# ab_v11.net
KiCad netlist of a schematic drawn in EAGLE
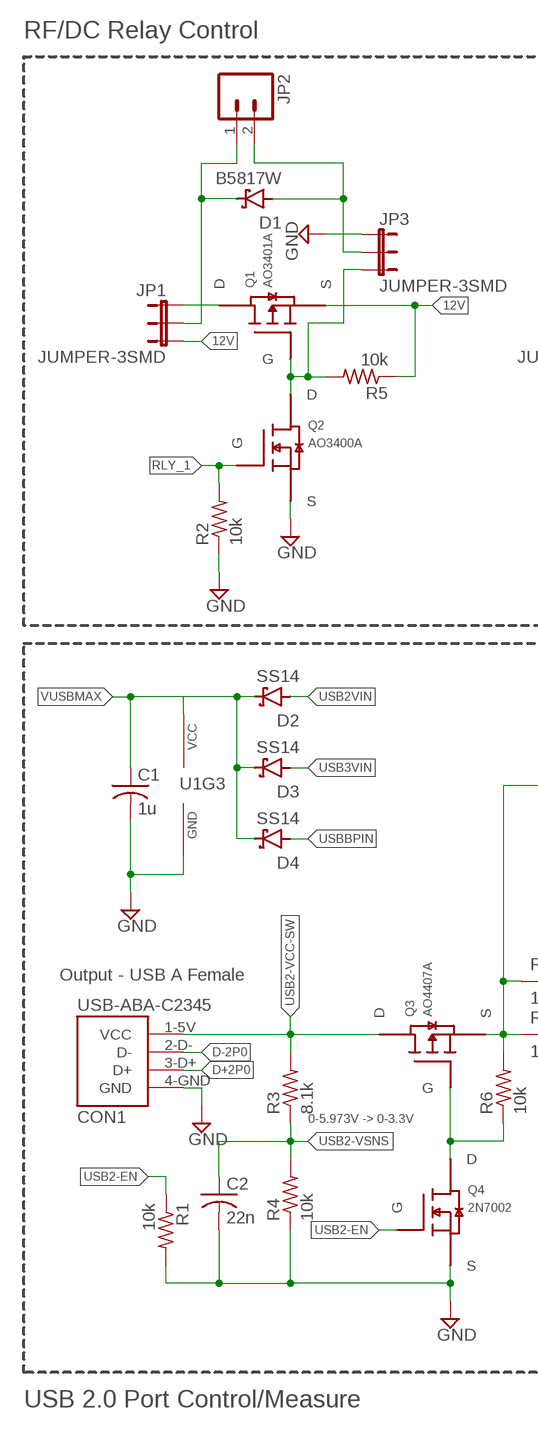
[diagram p0: schematic, sheet 1, part 1 of 2]
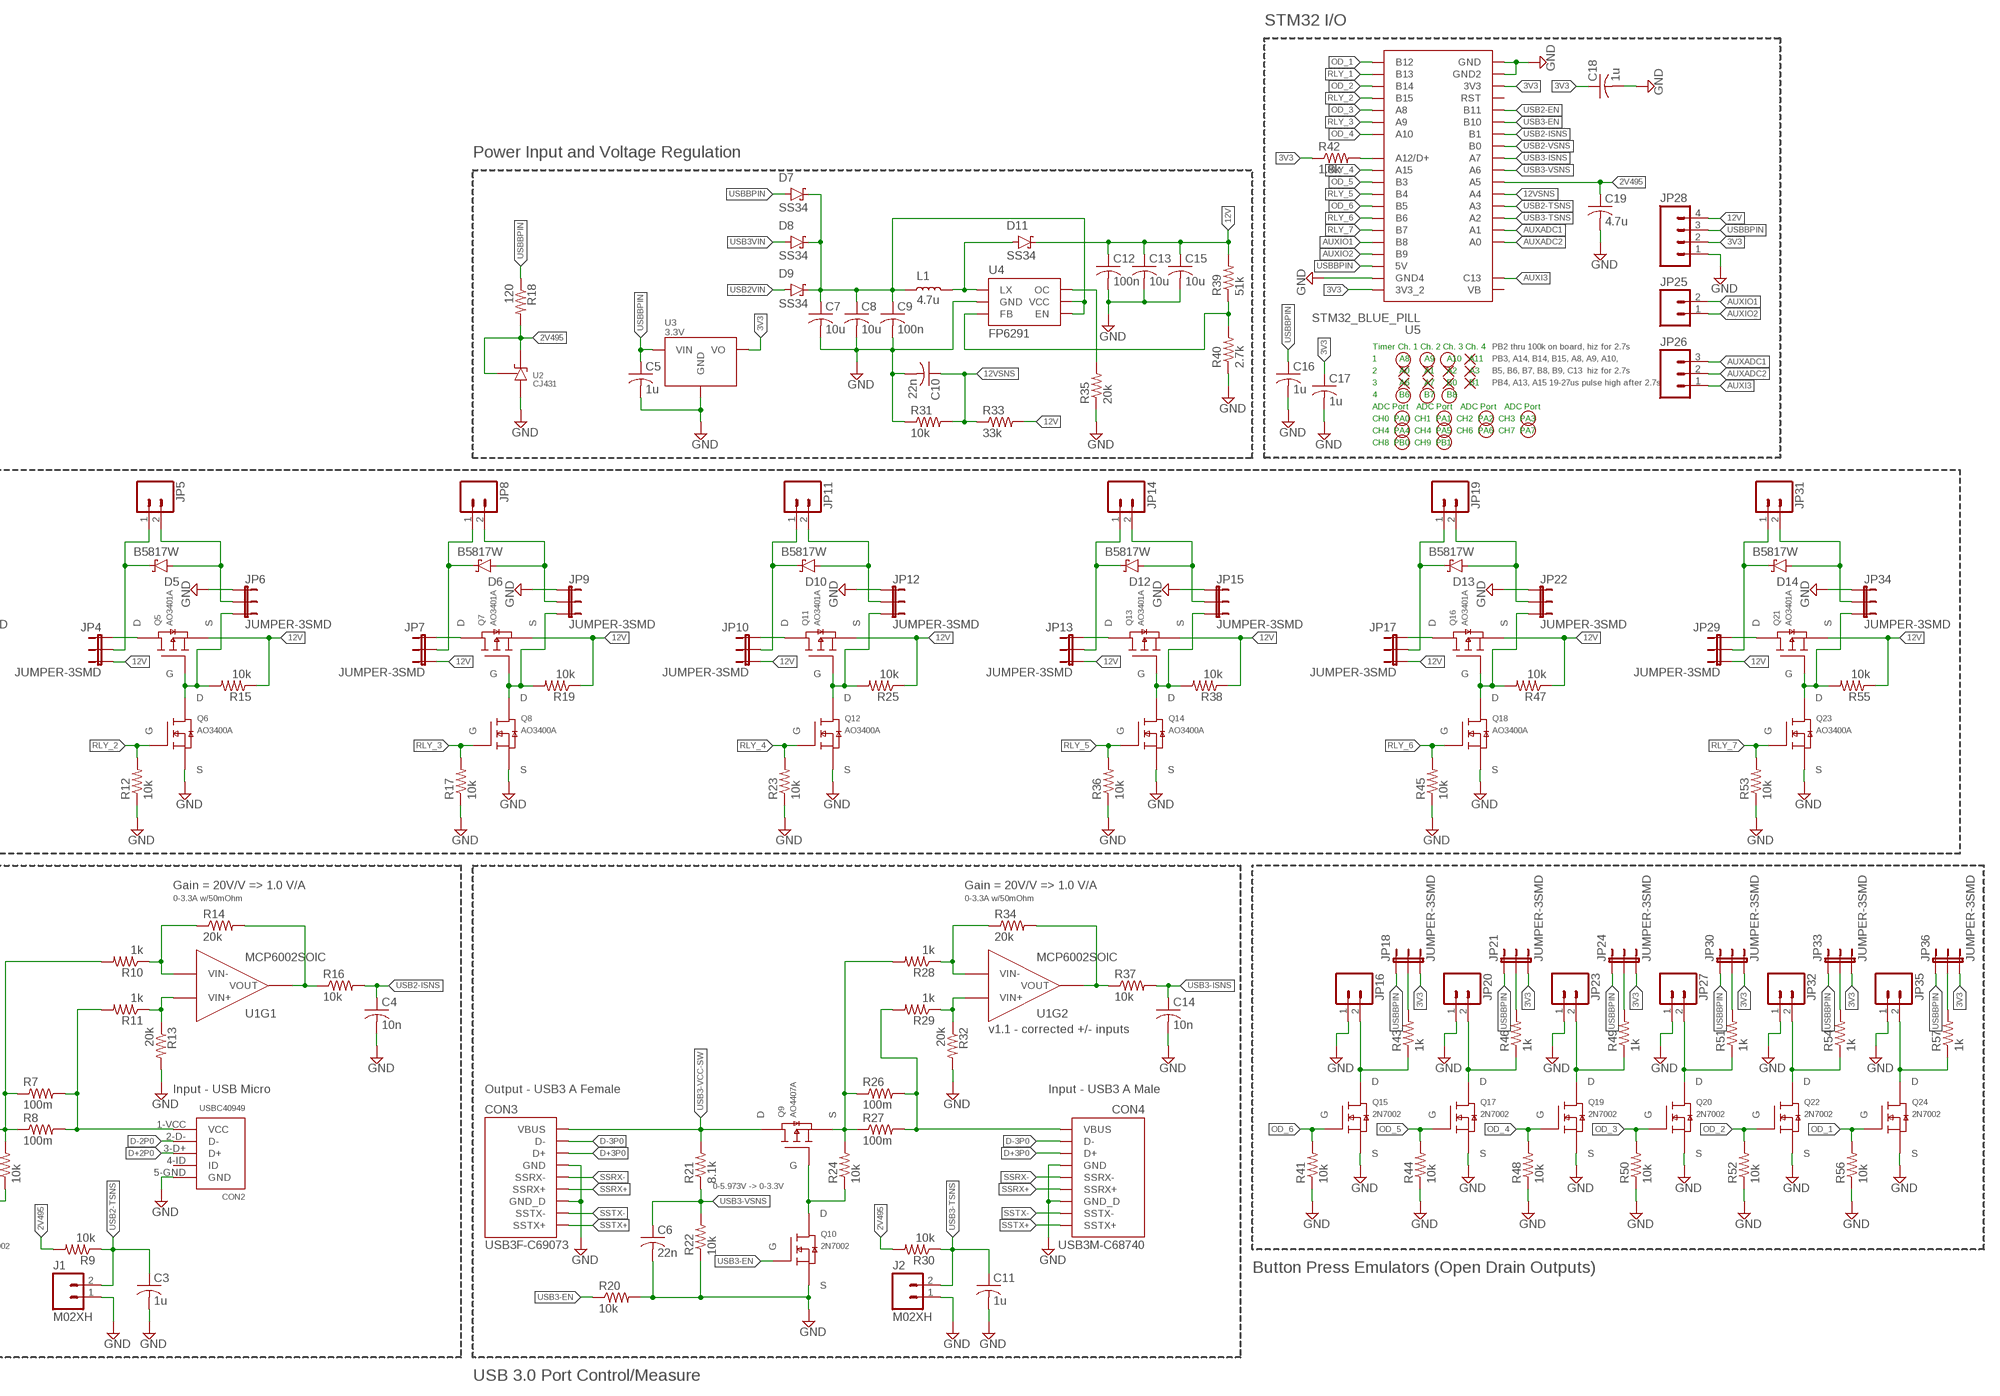
[diagram p1: schematic, sheet 1, part 2 of 2]

(export (version "E")
  (design (tool "Eeschema 10.0.6"))
  (components
    (comp (ref "C1")
      (value "1u")
      (footprint "eagle-import:C0402")
      (libsource (lib "eagle-import") (part "C-USC0402"))
    )
    (comp (ref "C2")
      (value "22n")
      (footprint "eagle-import:C0402")
      (libsource (lib "eagle-import") (part "C-USC0402"))
    )
    (comp (ref "C3")
      (value "1u")
      (footprint "eagle-import:C0402")
      (libsource (lib "eagle-import") (part "C-USC0402"))
    )
    (comp (ref "C4")
      (value "10n")
      (footprint "eagle-import:C0402")
      (libsource (lib "eagle-import") (part "C-USC0402"))
    )
    (comp (ref "C5")
      (value "1u")
      (footprint "eagle-import:C0402")
      (libsource (lib "eagle-import") (part "C-USC0402"))
    )
    (comp (ref "C6")
      (value "22n")
      (footprint "eagle-import:C0402")
      (libsource (lib "eagle-import") (part "C-USC0402"))
    )
    (comp (ref "C7")
      (value "10u")
      (footprint "eagle-import:C0603")
      (libsource (lib "eagle-import") (part "C-USC0603"))
    )
    (comp (ref "C8")
      (value "10u")
      (footprint "eagle-import:C0603")
      (libsource (lib "eagle-import") (part "C-USC0603"))
    )
    (comp (ref "C9")
      (value "100n")
      (footprint "eagle-import:C0402")
      (libsource (lib "eagle-import") (part "C-USC0402"))
    )
    (comp (ref "C10")
      (value "22n")
      (footprint "eagle-import:C0402")
      (libsource (lib "eagle-import") (part "C-USC0402"))
    )
    (comp (ref "C11")
      (value "1u")
      (footprint "eagle-import:C0402")
      (libsource (lib "eagle-import") (part "C-USC0402"))
    )
    (comp (ref "C12")
      (value "100n")
      (footprint "eagle-import:C0402")
      (libsource (lib "eagle-import") (part "C-USC0402"))
    )
    (comp (ref "C13")
      (value "10u")
      (footprint "eagle-import:C0805")
      (libsource (lib "eagle-import") (part "C-USC0805"))
    )
    (comp (ref "C14")
      (value "10n")
      (footprint "eagle-import:C0402")
      (libsource (lib "eagle-import") (part "C-USC0402"))
    )
    (comp (ref "C15")
      (value "10u")
      (footprint "eagle-import:C0805")
      (libsource (lib "eagle-import") (part "C-USC0805"))
    )
    (comp (ref "C16")
      (value "1u")
      (footprint "eagle-import:C0402")
      (libsource (lib "eagle-import") (part "C-USC0402"))
    )
    (comp (ref "C17")
      (value "1u")
      (footprint "eagle-import:C0402")
      (libsource (lib "eagle-import") (part "C-USC0402"))
    )
    (comp (ref "C18")
      (value "1u")
      (footprint "eagle-import:C0402")
      (libsource (lib "eagle-import") (part "C-USC0402"))
    )
    (comp (ref "C19")
      (value "4.7u")
      (footprint "eagle-import:C0402")
      (libsource (lib "eagle-import") (part "C-USC0402"))
    )
    (comp (ref "CON1")
      (value "USB-ABA-C2345")
      (footprint "eagle-import:USB_A_C2345")
      (libsource (lib "eagle-import") (part "USB-ABA-C2345"))
    )
    (comp (ref "CON2")
      (value "USBC40949")
      (footprint "eagle-import:MICRO_USB-B_C40949")
      (libsource (lib "eagle-import") (part "USBC40949"))
    )
    (comp (ref "CON3")
      (value "USB3F-C69073")
      (footprint "eagle-import:USB3-F-C69073")
      (libsource (lib "eagle-import") (part "USB3F-C69073"))
    )
    (comp (ref "CON4")
      (value "USB3M-C68740")
      (footprint "eagle-import:USB3-M-C68740")
      (libsource (lib "eagle-import") (part "USB3M-C68740"))
    )
    (comp (ref "D1")
      (value "B5817W")
      (footprint "eagle-import:SOD123W")
      (libsource (lib "eagle-import") (part "PMEG3020ER"))
    )
    (comp (ref "D2")
      (value "SS14")
      (footprint "eagle-import:SMA")
      (libsource (lib "eagle-import") (part "DIODE_SCHOTTKY_SMSSMA"))
    )
    (comp (ref "D3")
      (value "SS14")
      (footprint "eagle-import:SMA")
      (libsource (lib "eagle-import") (part "DIODE_SCHOTTKY_SMSSMA"))
    )
    (comp (ref "D4")
      (value "SS14")
      (footprint "eagle-import:SMA")
      (libsource (lib "eagle-import") (part "DIODE_SCHOTTKY_SMSSMA"))
    )
    (comp (ref "D5")
      (value "B5817W")
      (footprint "eagle-import:SOD123W")
      (libsource (lib "eagle-import") (part "PMEG3020ER"))
    )
    (comp (ref "D6")
      (value "B5817W")
      (footprint "eagle-import:SOD123W")
      (libsource (lib "eagle-import") (part "PMEG3020ER"))
    )
    (comp (ref "D7")
      (value "SS34")
      (footprint "eagle-import:SMA")
      (libsource (lib "eagle-import") (part "DIODE_SCHOTTKY_SMSSMA"))
    )
    (comp (ref "D8")
      (value "SS34")
      (footprint "eagle-import:SMA")
      (libsource (lib "eagle-import") (part "DIODE_SCHOTTKY_SMSSMA"))
    )
    (comp (ref "D9")
      (value "SS34")
      (footprint "eagle-import:SMA")
      (libsource (lib "eagle-import") (part "DIODE_SCHOTTKY_SMSSMA"))
    )
    (comp (ref "D10")
      (value "B5817W")
      (footprint "eagle-import:SOD123W")
      (libsource (lib "eagle-import") (part "PMEG3020ER"))
    )
    (comp (ref "D11")
      (value "SS34")
      (footprint "eagle-import:SMA")
      (libsource (lib "eagle-import") (part "DIODE_SCHOTTKY_SMSSMA"))
    )
    (comp (ref "D12")
      (value "B5817W")
      (footprint "eagle-import:SOD123W")
      (libsource (lib "eagle-import") (part "PMEG3020ER"))
    )
    (comp (ref "D13")
      (value "B5817W")
      (footprint "eagle-import:SOD123W")
      (libsource (lib "eagle-import") (part "PMEG3020ER"))
    )
    (comp (ref "D14")
      (value "B5817W")
      (footprint "eagle-import:SOD123W")
      (libsource (lib "eagle-import") (part "PMEG3020ER"))
    )
    (comp (ref "J1")
      (value "M02XH")
      (footprint "eagle-import:B2B-XH-A")
      (libsource (lib "eagle-import") (part "M02XH"))
    )
    (comp (ref "J2")
      (value "M02XH")
      (footprint "eagle-import:B2B-XH-A")
      (libsource (lib "eagle-import") (part "M02XH"))
    )
    (comp (ref "JP1")
      (value "JUMPER-3SMD")
      (footprint "eagle-import:SJ_3")
      (libsource (lib "eagle-import") (part "JUMPER-3SMD"))
    )
    (comp (ref "JP2")
      (value "M02PTH")
      (footprint "eagle-import:1X02")
      (libsource (lib "eagle-import") (part "M02PTH"))
    )
    (comp (ref "JP3")
      (value "JUMPER-3SMD")
      (footprint "eagle-import:SJ_3")
      (libsource (lib "eagle-import") (part "JUMPER-3SMD"))
    )
    (comp (ref "JP4")
      (value "JUMPER-3SMD")
      (footprint "eagle-import:SJ_3")
      (libsource (lib "eagle-import") (part "JUMPER-3SMD"))
    )
    (comp (ref "JP5")
      (value "M02PTH")
      (footprint "eagle-import:1X02")
      (libsource (lib "eagle-import") (part "M02PTH"))
    )
    (comp (ref "JP6")
      (value "JUMPER-3SMD")
      (footprint "eagle-import:SJ_3")
      (libsource (lib "eagle-import") (part "JUMPER-3SMD"))
    )
    (comp (ref "JP7")
      (value "JUMPER-3SMD")
      (footprint "eagle-import:SJ_3")
      (libsource (lib "eagle-import") (part "JUMPER-3SMD"))
    )
    (comp (ref "JP8")
      (value "M02PTH")
      (footprint "eagle-import:1X02")
      (libsource (lib "eagle-import") (part "M02PTH"))
    )
    (comp (ref "JP9")
      (value "JUMPER-3SMD")
      (footprint "eagle-import:SJ_3")
      (libsource (lib "eagle-import") (part "JUMPER-3SMD"))
    )
    (comp (ref "JP10")
      (value "JUMPER-3SMD")
      (footprint "eagle-import:SJ_3")
      (libsource (lib "eagle-import") (part "JUMPER-3SMD"))
    )
    (comp (ref "JP11")
      (value "M02PTH")
      (footprint "eagle-import:1X02")
      (libsource (lib "eagle-import") (part "M02PTH"))
    )
    (comp (ref "JP12")
      (value "JUMPER-3SMD")
      (footprint "eagle-import:SJ_3")
      (libsource (lib "eagle-import") (part "JUMPER-3SMD"))
    )
    (comp (ref "JP13")
      (value "JUMPER-3SMD")
      (footprint "eagle-import:SJ_3")
      (libsource (lib "eagle-import") (part "JUMPER-3SMD"))
    )
    (comp (ref "JP14")
      (value "M02PTH")
      (footprint "eagle-import:1X02")
      (libsource (lib "eagle-import") (part "M02PTH"))
    )
    (comp (ref "JP15")
      (value "JUMPER-3SMD")
      (footprint "eagle-import:SJ_3")
      (libsource (lib "eagle-import") (part "JUMPER-3SMD"))
    )
    (comp (ref "JP16")
      (value "M02PTH")
      (footprint "eagle-import:1X02")
      (libsource (lib "eagle-import") (part "M02PTH"))
    )
    (comp (ref "JP17")
      (value "JUMPER-3SMD")
      (footprint "eagle-import:SJ_3")
      (libsource (lib "eagle-import") (part "JUMPER-3SMD"))
    )
    (comp (ref "JP18")
      (value "JUMPER-3SMD")
      (footprint "eagle-import:SJ_3")
      (libsource (lib "eagle-import") (part "JUMPER-3SMD"))
    )
    (comp (ref "JP19")
      (value "M02PTH")
      (footprint "eagle-import:1X02")
      (libsource (lib "eagle-import") (part "M02PTH"))
    )
    (comp (ref "JP20")
      (value "M02PTH")
      (footprint "eagle-import:1X02")
      (libsource (lib "eagle-import") (part "M02PTH"))
    )
    (comp (ref "JP21")
      (value "JUMPER-3SMD")
      (footprint "eagle-import:SJ_3")
      (libsource (lib "eagle-import") (part "JUMPER-3SMD"))
    )
    (comp (ref "JP22")
      (value "JUMPER-3SMD")
      (footprint "eagle-import:SJ_3")
      (libsource (lib "eagle-import") (part "JUMPER-3SMD"))
    )
    (comp (ref "JP23")
      (value "M02PTH")
      (footprint "eagle-import:1X02")
      (libsource (lib "eagle-import") (part "M02PTH"))
    )
    (comp (ref "JP24")
      (value "JUMPER-3SMD")
      (footprint "eagle-import:SJ_3")
      (libsource (lib "eagle-import") (part "JUMPER-3SMD"))
    )
    (comp (ref "JP25")
      (value "M02PTH")
      (footprint "eagle-import:1X02")
      (libsource (lib "eagle-import") (part "M02PTH"))
    )
    (comp (ref "JP26")
      (value "M03PTH")
      (footprint "eagle-import:1X03")
      (libsource (lib "eagle-import") (part "M03PTH"))
    )
    (comp (ref "JP27")
      (value "M02PTH")
      (footprint "eagle-import:1X02")
      (libsource (lib "eagle-import") (part "M02PTH"))
    )
    (comp (ref "JP28")
      (value "M04PTH")
      (footprint "eagle-import:1X04")
      (libsource (lib "eagle-import") (part "M04PTH"))
    )
    (comp (ref "JP29")
      (value "JUMPER-3SMD")
      (footprint "eagle-import:SJ_3")
      (libsource (lib "eagle-import") (part "JUMPER-3SMD"))
    )
    (comp (ref "JP30")
      (value "JUMPER-3SMD")
      (footprint "eagle-import:SJ_3")
      (libsource (lib "eagle-import") (part "JUMPER-3SMD"))
    )
    (comp (ref "JP31")
      (value "M02PTH")
      (footprint "eagle-import:1X02")
      (libsource (lib "eagle-import") (part "M02PTH"))
    )
    (comp (ref "JP32")
      (value "M02PTH")
      (footprint "eagle-import:1X02")
      (libsource (lib "eagle-import") (part "M02PTH"))
    )
    (comp (ref "JP33")
      (value "JUMPER-3SMD")
      (footprint "eagle-import:SJ_3")
      (libsource (lib "eagle-import") (part "JUMPER-3SMD"))
    )
    (comp (ref "JP34")
      (value "JUMPER-3SMD")
      (footprint "eagle-import:SJ_3")
      (libsource (lib "eagle-import") (part "JUMPER-3SMD"))
    )
    (comp (ref "JP35")
      (value "M02PTH")
      (footprint "eagle-import:1X02")
      (libsource (lib "eagle-import") (part "M02PTH"))
    )
    (comp (ref "JP36")
      (value "JUMPER-3SMD")
      (footprint "eagle-import:SJ_3")
      (libsource (lib "eagle-import") (part "JUMPER-3SMD"))
    )
    (comp (ref "L1")
      (value "4.7u")
      (footprint "eagle-import:INDUCTOR_6X6")
      (libsource (lib "eagle-import") (part "INDUCTOR6X6"))
    )
    (comp (ref "Q1")
      (value "AO3401A")
      (footprint "eagle-import:SOT23")
      (libsource (lib "eagle-import") (part "AO3401A"))
    )
    (comp (ref "Q2")
      (value "AO3400A")
      (footprint "eagle-import:SOT23")
      (libsource (lib "eagle-import") (part "2N7002P"))
    )
    (comp (ref "Q3")
      (value "AO4407A")
      (footprint "eagle-import:8-SOIC")
      (libsource (lib "eagle-import") (part "P-MOSFET-SOIC8"))
    )
    (comp (ref "Q4")
      (value "2N7002")
      (footprint "eagle-import:SOT23")
      (libsource (lib "eagle-import") (part "2N7002P"))
    )
    (comp (ref "Q5")
      (value "AO3401A")
      (footprint "eagle-import:SOT23")
      (libsource (lib "eagle-import") (part "AO3401A"))
    )
    (comp (ref "Q6")
      (value "AO3400A")
      (footprint "eagle-import:SOT23")
      (libsource (lib "eagle-import") (part "2N7002P"))
    )
    (comp (ref "Q7")
      (value "AO3401A")
      (footprint "eagle-import:SOT23")
      (libsource (lib "eagle-import") (part "AO3401A"))
    )
    (comp (ref "Q8")
      (value "AO3400A")
      (footprint "eagle-import:SOT23")
      (libsource (lib "eagle-import") (part "2N7002P"))
    )
    (comp (ref "Q9")
      (value "AO4407A")
      (footprint "eagle-import:8-SOIC")
      (libsource (lib "eagle-import") (part "P-MOSFET-SOIC8"))
    )
    (comp (ref "Q10")
      (value "2N7002")
      (footprint "eagle-import:SOT23")
      (libsource (lib "eagle-import") (part "2N7002P"))
    )
    (comp (ref "Q11")
      (value "AO3401A")
      (footprint "eagle-import:SOT23")
      (libsource (lib "eagle-import") (part "AO3401A"))
    )
    (comp (ref "Q12")
      (value "AO3400A")
      (footprint "eagle-import:SOT23")
      (libsource (lib "eagle-import") (part "2N7002P"))
    )
    (comp (ref "Q13")
      (value "AO3401A")
      (footprint "eagle-import:SOT23")
      (libsource (lib "eagle-import") (part "AO3401A"))
    )
    (comp (ref "Q14")
      (value "AO3400A")
      (footprint "eagle-import:SOT23")
      (libsource (lib "eagle-import") (part "2N7002P"))
    )
    (comp (ref "Q15")
      (value "2N7002")
      (footprint "eagle-import:SOT23")
      (libsource (lib "eagle-import") (part "2N7002P"))
    )
    (comp (ref "Q16")
      (value "AO3401A")
      (footprint "eagle-import:SOT23")
      (libsource (lib "eagle-import") (part "AO3401A"))
    )
    (comp (ref "Q17")
      (value "2N7002")
      (footprint "eagle-import:SOT23")
      (libsource (lib "eagle-import") (part "2N7002P"))
    )
    (comp (ref "Q18")
      (value "AO3400A")
      (footprint "eagle-import:SOT23")
      (libsource (lib "eagle-import") (part "2N7002P"))
    )
    (comp (ref "Q19")
      (value "2N7002")
      (footprint "eagle-import:SOT23")
      (libsource (lib "eagle-import") (part "2N7002P"))
    )
    (comp (ref "Q20")
      (value "2N7002")
      (footprint "eagle-import:SOT23")
      (libsource (lib "eagle-import") (part "2N7002P"))
    )
    (comp (ref "Q21")
      (value "AO3401A")
      (footprint "eagle-import:SOT23")
      (libsource (lib "eagle-import") (part "AO3401A"))
    )
    (comp (ref "Q22")
      (value "2N7002")
      (footprint "eagle-import:SOT23")
      (libsource (lib "eagle-import") (part "2N7002P"))
    )
    (comp (ref "Q23")
      (value "AO3400A")
      (footprint "eagle-import:SOT23")
      (libsource (lib "eagle-import") (part "2N7002P"))
    )
    (comp (ref "Q24")
      (value "2N7002")
      (footprint "eagle-import:SOT23")
      (libsource (lib "eagle-import") (part "2N7002P"))
    )
    (comp (ref "R1")
      (value "10k")
      (footprint "eagle-import:R0402")
      (libsource (lib "eagle-import") (part "R-US_R0402"))
    )
    (comp (ref "R2")
      (value "10k")
      (footprint "eagle-import:R0402")
      (libsource (lib "eagle-import") (part "R-US_R0402"))
    )
    (comp (ref "R3")
      (value "8.1k")
      (footprint "eagle-import:R0402")
      (libsource (lib "eagle-import") (part "R-US_R0402"))
    )
    (comp (ref "R4")
      (value "10k")
      (footprint "eagle-import:R0402")
      (libsource (lib "eagle-import") (part "R-US_R0402"))
    )
    (comp (ref "R5")
      (value "10k")
      (footprint "eagle-import:R0402")
      (libsource (lib "eagle-import") (part "R-US_R0402"))
    )
    (comp (ref "R6")
      (value "10k")
      (footprint "eagle-import:R0402")
      (libsource (lib "eagle-import") (part "R-US_R0402"))
    )
    (comp (ref "R7")
      (value "100m")
      (footprint "eagle-import:R1206")
      (libsource (lib "eagle-import") (part "R-US_R1206"))
    )
    (comp (ref "R8")
      (value "100m")
      (footprint "eagle-import:R1206")
      (libsource (lib "eagle-import") (part "R-US_R1206"))
    )
    (comp (ref "R9")
      (value "10k")
      (footprint "eagle-import:R0402")
      (libsource (lib "eagle-import") (part "R-US_R0402"))
    )
    (comp (ref "R10")
      (value "1k")
      (footprint "eagle-import:R0402")
      (libsource (lib "eagle-import") (part "R-US_R0402"))
    )
    (comp (ref "R11")
      (value "1k")
      (footprint "eagle-import:R0402")
      (libsource (lib "eagle-import") (part "R-US_R0402"))
    )
    (comp (ref "R12")
      (value "10k")
      (footprint "eagle-import:R0402")
      (libsource (lib "eagle-import") (part "R-US_R0402"))
    )
    (comp (ref "R13")
      (value "20k")
      (footprint "eagle-import:R0402")
      (libsource (lib "eagle-import") (part "R-US_R0402"))
    )
    (comp (ref "R14")
      (value "20k")
      (footprint "eagle-import:R0402")
      (libsource (lib "eagle-import") (part "R-US_R0402"))
    )
    (comp (ref "R15")
      (value "10k")
      (footprint "eagle-import:R0402")
      (libsource (lib "eagle-import") (part "R-US_R0402"))
    )
    (comp (ref "R16")
      (value "10k")
      (footprint "eagle-import:R0402")
      (libsource (lib "eagle-import") (part "R-US_R0402"))
    )
    (comp (ref "R17")
      (value "10k")
      (footprint "eagle-import:R0402")
      (libsource (lib "eagle-import") (part "R-US_R0402"))
    )
    (comp (ref "R18")
      (value "120")
      (footprint "eagle-import:R0402")
      (libsource (lib "eagle-import") (part "R-US_R0402"))
    )
    (comp (ref "R19")
      (value "10k")
      (footprint "eagle-import:R0402")
      (libsource (lib "eagle-import") (part "R-US_R0402"))
    )
    (comp (ref "R20")
      (value "10k")
      (footprint "eagle-import:R0402")
      (libsource (lib "eagle-import") (part "R-US_R0402"))
    )
    (comp (ref "R21")
      (value "8.1k")
      (footprint "eagle-import:R0402")
      (libsource (lib "eagle-import") (part "R-US_R0402"))
    )
    (comp (ref "R22")
      (value "10k")
      (footprint "eagle-import:R0402")
      (libsource (lib "eagle-import") (part "R-US_R0402"))
    )
    (comp (ref "R23")
      (value "10k")
      (footprint "eagle-import:R0402")
      (libsource (lib "eagle-import") (part "R-US_R0402"))
    )
    (comp (ref "R24")
      (value "10k")
      (footprint "eagle-import:R0402")
      (libsource (lib "eagle-import") (part "R-US_R0402"))
    )
    (comp (ref "R25")
      (value "10k")
      (footprint "eagle-import:R0402")
      (libsource (lib "eagle-import") (part "R-US_R0402"))
    )
    (comp (ref "R26")
      (value "100m")
      (footprint "eagle-import:R1206")
      (libsource (lib "eagle-import") (part "R-US_R1206"))
    )
    (comp (ref "R27")
      (value "100m")
      (footprint "eagle-import:R1206")
      (libsource (lib "eagle-import") (part "R-US_R1206"))
    )
    (comp (ref "R28")
      (value "1k")
      (footprint "eagle-import:R0402")
      (libsource (lib "eagle-import") (part "R-US_R0402"))
    )
    (comp (ref "R29")
      (value "1k")
      (footprint "eagle-import:R0402")
      (libsource (lib "eagle-import") (part "R-US_R0402"))
    )
    (comp (ref "R30")
      (value "10k")
      (footprint "eagle-import:R0402")
      (libsource (lib "eagle-import") (part "R-US_R0402"))
    )
    (comp (ref "R31")
      (value "10k")
      (footprint "eagle-import:R0402")
      (libsource (lib "eagle-import") (part "R-US_R0402"))
    )
    (comp (ref "R32")
      (value "20k")
      (footprint "eagle-import:R0402")
      (libsource (lib "eagle-import") (part "R-US_R0402"))
    )
    (comp (ref "R33")
      (value "33k")
      (footprint "eagle-import:R0402")
      (libsource (lib "eagle-import") (part "R-US_R0402"))
    )
    (comp (ref "R34")
      (value "20k")
      (footprint "eagle-import:R0402")
      (libsource (lib "eagle-import") (part "R-US_R0402"))
    )
    (comp (ref "R35")
      (value "20k")
      (footprint "eagle-import:R0402")
      (libsource (lib "eagle-import") (part "R-US_R0402"))
    )
    (comp (ref "R36")
      (value "10k")
      (footprint "eagle-import:R0402")
      (libsource (lib "eagle-import") (part "R-US_R0402"))
    )
    (comp (ref "R37")
      (value "10k")
      (footprint "eagle-import:R0402")
      (libsource (lib "eagle-import") (part "R-US_R0402"))
    )
    (comp (ref "R38")
      (value "10k")
      (footprint "eagle-import:R0402")
      (libsource (lib "eagle-import") (part "R-US_R0402"))
    )
    (comp (ref "R39")
      (value "51k")
      (footprint "eagle-import:R0402")
      (libsource (lib "eagle-import") (part "R-US_R0402"))
    )
    (comp (ref "R40")
      (value "2.7k")
      (footprint "eagle-import:R0402")
      (libsource (lib "eagle-import") (part "R-US_R0402"))
    )
    (comp (ref "R41")
      (value "10k")
      (footprint "eagle-import:R0402")
      (libsource (lib "eagle-import") (part "R-US_R0402"))
    )
    (comp (ref "R42")
      (value "1.8k")
      (footprint "eagle-import:R0402")
      (libsource (lib "eagle-import") (part "R-US_R0402"))
    )
    (comp (ref "R43")
      (value "1k")
      (footprint "eagle-import:R0402")
      (libsource (lib "eagle-import") (part "R-US_R0402"))
    )
    (comp (ref "R44")
      (value "10k")
      (footprint "eagle-import:R0402")
      (libsource (lib "eagle-import") (part "R-US_R0402"))
    )
    (comp (ref "R45")
      (value "10k")
      (footprint "eagle-import:R0402")
      (libsource (lib "eagle-import") (part "R-US_R0402"))
    )
    (comp (ref "R46")
      (value "1k")
      (footprint "eagle-import:R0402")
      (libsource (lib "eagle-import") (part "R-US_R0402"))
    )
    (comp (ref "R47")
      (value "10k")
      (footprint "eagle-import:R0402")
      (libsource (lib "eagle-import") (part "R-US_R0402"))
    )
    (comp (ref "R48")
      (value "10k")
      (footprint "eagle-import:R0402")
      (libsource (lib "eagle-import") (part "R-US_R0402"))
    )
    (comp (ref "R49")
      (value "1k")
      (footprint "eagle-import:R0402")
      (libsource (lib "eagle-import") (part "R-US_R0402"))
    )
    (comp (ref "R50")
      (value "10k")
      (footprint "eagle-import:R0402")
      (libsource (lib "eagle-import") (part "R-US_R0402"))
    )
    (comp (ref "R51")
      (value "1k")
      (footprint "eagle-import:R0402")
      (libsource (lib "eagle-import") (part "R-US_R0402"))
    )
    (comp (ref "R52")
      (value "10k")
      (footprint "eagle-import:R0402")
      (libsource (lib "eagle-import") (part "R-US_R0402"))
    )
    (comp (ref "R53")
      (value "10k")
      (footprint "eagle-import:R0402")
      (libsource (lib "eagle-import") (part "R-US_R0402"))
    )
    (comp (ref "R54")
      (value "1k")
      (footprint "eagle-import:R0402")
      (libsource (lib "eagle-import") (part "R-US_R0402"))
    )
    (comp (ref "R55")
      (value "10k")
      (footprint "eagle-import:R0402")
      (libsource (lib "eagle-import") (part "R-US_R0402"))
    )
    (comp (ref "R56")
      (value "10k")
      (footprint "eagle-import:R0402")
      (libsource (lib "eagle-import") (part "R-US_R0402"))
    )
    (comp (ref "R57")
      (value "1k")
      (footprint "eagle-import:R0402")
      (libsource (lib "eagle-import") (part "R-US_R0402"))
    )
    (comp (ref "U1")
      (value "MCP6002SOIC")
      (footprint "eagle-import:8-SOIC")
      (libsource (lib "eagle-import") (part "MCP6002SOIC"))
    )
    (comp (ref "U2")
      (value "CJ431")
      (footprint "eagle-import:SOT23")
      (libsource (lib "eagle-import") (part "TL431SOT23"))
    )
    (comp (ref "U3")
      (value "3.3V")
      (footprint "eagle-import:SOT-89")
      (libsource (lib "eagle-import") (part "AP1117UR133-B"))
    )
    (comp (ref "U4")
      (value "FP6291")
      (footprint "eagle-import:SOT23-6")
      (libsource (lib "eagle-import") (part "FP6291"))
    )
    (comp (ref "U5")
      (value "STM32_BLUE_PILL")
      (footprint "eagle-import:STM32_BLUE_PILL_USABLE")
      (libsource (lib "eagle-import") (part "STM32_BLUE_PILL"))
    )
  )
  (nets
    (net (code "1") (name "2V495") (class "Default")
      (node (ref "C19") (pin "1") (pinfunction "1_1") (pintype "passive"))
      (node (ref "R18") (pin "2") (pinfunction "2_2") (pintype "passive"))
      (node (ref "R30") (pin "2") (pinfunction "2_2") (pintype "passive"))
      (node (ref "R9") (pin "2") (pinfunction "2_2") (pintype "passive"))
      (node (ref "U2") (pin "1") (pinfunction "K_1") (pintype "passive"))
      (node (ref "U2") (pin "2") (pinfunction "REF_2") (pintype "passive"))
      (node (ref "U5") (pin "A5") (pinfunction "A5_A5") (pintype "bidirectional"))
    )
    (net (code "2") (name "3V3") (class "Default")
      (node (ref "C17") (pin "1") (pinfunction "1_1") (pintype "passive"))
      (node (ref "C18") (pin "1") (pinfunction "1_1") (pintype "passive"))
      (node (ref "JP18") (pin "3") (pinfunction "3_3") (pintype "passive"))
      (node (ref "JP21") (pin "3") (pinfunction "3_3") (pintype "passive"))
      (node (ref "JP24") (pin "3") (pinfunction "3_3") (pintype "passive"))
      (node (ref "JP28") (pin "2") (pinfunction "2_2") (pintype "passive"))
      (node (ref "JP30") (pin "3") (pinfunction "3_3") (pintype "passive"))
      (node (ref "JP33") (pin "3") (pinfunction "3_3") (pintype "passive"))
      (node (ref "JP36") (pin "3") (pinfunction "3_3") (pintype "passive"))
      (node (ref "R42") (pin "1") (pinfunction "1_1") (pintype "passive"))
      (node (ref "U3") (pin "1") (pinfunction "VO_1") (pintype "bidirectional"))
      (node (ref "U5") (pin "3V3") (pinfunction "3V3_3V3") (pintype "bidirectional"))
      (node (ref "U5") (pin "3V3_2") (pinfunction "3V3_2_3V3_2") (pintype "bidirectional"))
    )
    (net (code "3") (name "12V") (class "Default")
      (node (ref "C12") (pin "1") (pinfunction "1_1") (pintype "passive"))
      (node (ref "C13") (pin "1") (pinfunction "1_1") (pintype "passive"))
      (node (ref "C15") (pin "1") (pinfunction "1_1") (pintype "passive"))
      (node (ref "D11") (pin "K") (pinfunction "CATHODE_K") (pintype "passive"))
      (node (ref "JP1") (pin "3") (pinfunction "3_3") (pintype "passive"))
      (node (ref "JP10") (pin "3") (pinfunction "3_3") (pintype "passive"))
      (node (ref "JP13") (pin "3") (pinfunction "3_3") (pintype "passive"))
      (node (ref "JP17") (pin "3") (pinfunction "3_3") (pintype "passive"))
      (node (ref "JP28") (pin "4") (pinfunction "4_4") (pintype "passive"))
      (node (ref "JP29") (pin "3") (pinfunction "3_3") (pintype "passive"))
      (node (ref "JP4") (pin "3") (pinfunction "3_3") (pintype "passive"))
      (node (ref "JP7") (pin "3") (pinfunction "3_3") (pintype "passive"))
      (node (ref "Q1") (pin "2") (pinfunction "S_2") (pintype "bidirectional"))
      (node (ref "Q11") (pin "2") (pinfunction "S_2") (pintype "bidirectional"))
      (node (ref "Q13") (pin "2") (pinfunction "S_2") (pintype "bidirectional"))
      (node (ref "Q16") (pin "2") (pinfunction "S_2") (pintype "bidirectional"))
      (node (ref "Q21") (pin "2") (pinfunction "S_2") (pintype "bidirectional"))
      (node (ref "Q5") (pin "2") (pinfunction "S_2") (pintype "bidirectional"))
      (node (ref "Q7") (pin "2") (pinfunction "S_2") (pintype "bidirectional"))
      (node (ref "R15") (pin "1") (pinfunction "1_1") (pintype "passive"))
      (node (ref "R19") (pin "1") (pinfunction "1_1") (pintype "passive"))
      (node (ref "R25") (pin "1") (pinfunction "1_1") (pintype "passive"))
      (node (ref "R33") (pin "2") (pinfunction "2_2") (pintype "passive"))
      (node (ref "R38") (pin "1") (pinfunction "1_1") (pintype "passive"))
      (node (ref "R39") (pin "2") (pinfunction "2_2") (pintype "passive"))
      (node (ref "R47") (pin "1") (pinfunction "1_1") (pintype "passive"))
      (node (ref "R5") (pin "1") (pinfunction "1_1") (pintype "passive"))
      (node (ref "R55") (pin "1") (pinfunction "1_1") (pintype "passive"))
    )
    (net (code "4") (name "12VSNS") (class "Default")
      (node (ref "C10") (pin "1") (pinfunction "1_1") (pintype "passive"))
      (node (ref "R31") (pin "2") (pinfunction "2_2") (pintype "passive"))
      (node (ref "R33") (pin "1") (pinfunction "1_1") (pintype "passive"))
      (node (ref "U5") (pin "A4") (pinfunction "A4_A4") (pintype "bidirectional"))
    )
    (net (code "5") (name "AUXADC1") (class "Default")
      (node (ref "JP26") (pin "3") (pinfunction "3_3") (pintype "passive"))
      (node (ref "U5") (pin "A1") (pinfunction "A1_A1") (pintype "bidirectional"))
    )
    (net (code "6") (name "AUXADC2") (class "Default")
      (node (ref "JP26") (pin "2") (pinfunction "2_2") (pintype "passive"))
      (node (ref "U5") (pin "A0") (pinfunction "A0_A0") (pintype "bidirectional"))
    )
    (net (code "7") (name "AUXI3") (class "Default")
      (node (ref "JP26") (pin "1") (pinfunction "1_1") (pintype "passive"))
      (node (ref "U5") (pin "C13") (pinfunction "C13_C13") (pintype "bidirectional"))
    )
    (net (code "8") (name "AUXIO1") (class "Default")
      (node (ref "JP25") (pin "2") (pinfunction "2_2") (pintype "passive"))
      (node (ref "U5") (pin "B8") (pinfunction "B8_B8") (pintype "bidirectional"))
    )
    (net (code "9") (name "AUXIO2") (class "Default")
      (node (ref "JP25") (pin "1") (pinfunction "1_1") (pintype "passive"))
      (node (ref "U5") (pin "B9") (pinfunction "B9_B9") (pintype "bidirectional"))
    )
    (net (code "10") (name "D+2P0") (class "Default")
      (node (ref "CON1") (pin "3-D+") (pinfunction "D+_3-D+") (pintype "bidirectional"))
      (node (ref "CON2") (pin "3-D+") (pinfunction "D+_3-D+") (pintype "bidirectional"))
    )
    (net (code "11") (name "D+3P0") (class "Default")
      (node (ref "CON3") (pin "3-D+") (pinfunction "D+_3-D+") (pintype "bidirectional"))
      (node (ref "CON4") (pin "3-D+") (pinfunction "D+_3-D+") (pintype "bidirectional"))
    )
    (net (code "12") (name "D-2P0") (class "Default")
      (node (ref "CON1") (pin "2-D-") (pinfunction "D-_2-D-") (pintype "bidirectional"))
      (node (ref "CON2") (pin "2-D-") (pinfunction "D-_2-D-") (pintype "bidirectional"))
    )
    (net (code "13") (name "D-3P0") (class "Default")
      (node (ref "CON3") (pin "2-D-") (pinfunction "D-_2-D-") (pintype "bidirectional"))
      (node (ref "CON4") (pin "2-D-") (pinfunction "D-_2-D-") (pintype "bidirectional"))
    )
    (net (code "14") (name "GND") (class "Default")
      (node (ref "C1") (pin "2") (pinfunction "2_2") (pintype "passive"))
      (node (ref "C10") (pin "2") (pinfunction "2_2") (pintype "passive"))
      (node (ref "C11") (pin "2") (pinfunction "2_2") (pintype "passive"))
      (node (ref "C12") (pin "2") (pinfunction "2_2") (pintype "passive"))
      (node (ref "C13") (pin "2") (pinfunction "2_2") (pintype "passive"))
      (node (ref "C14") (pin "2") (pinfunction "2_2") (pintype "passive"))
      (node (ref "C15") (pin "2") (pinfunction "2_2") (pintype "passive"))
      (node (ref "C16") (pin "2") (pinfunction "2_2") (pintype "passive"))
      (node (ref "C17") (pin "2") (pinfunction "2_2") (pintype "passive"))
      (node (ref "C18") (pin "2") (pinfunction "2_2") (pintype "passive"))
      (node (ref "C19") (pin "2") (pinfunction "2_2") (pintype "passive"))
      (node (ref "C2") (pin "2") (pinfunction "2_2") (pintype "passive"))
      (node (ref "C3") (pin "2") (pinfunction "2_2") (pintype "passive"))
      (node (ref "C4") (pin "2") (pinfunction "2_2") (pintype "passive"))
      (node (ref "C5") (pin "2") (pinfunction "2_2") (pintype "passive"))
      (node (ref "C6") (pin "2") (pinfunction "2_2") (pintype "passive"))
      (node (ref "C7") (pin "2") (pinfunction "2_2") (pintype "passive"))
      (node (ref "C8") (pin "2") (pinfunction "2_2") (pintype "passive"))
      (node (ref "C9") (pin "2") (pinfunction "2_2") (pintype "passive"))
      (node (ref "CON1") (pin "4-GND") (pinfunction "GND_4-GND") (pintype "bidirectional"))
      (node (ref "CON2") (pin "5-GND") (pinfunction "GND_5-GND") (pintype "bidirectional"))
      (node (ref "CON3") (pin "4-GND") (pinfunction "GND_4-GND") (pintype "bidirectional"))
      (node (ref "CON3") (pin "7-GND") (pinfunction "GND_D_7-GND") (pintype "bidirectional"))
      (node (ref "CON4") (pin "4-GND") (pinfunction "GND_4-GND") (pintype "bidirectional"))
      (node (ref "CON4") (pin "7-GNDD") (pinfunction "GND_D_7-GNDD") (pintype "bidirectional"))
      (node (ref "J1") (pin "1") (pinfunction "1_1") (pintype "passive"))
      (node (ref "J2") (pin "1") (pinfunction "1_1") (pintype "passive"))
      (node (ref "JP12") (pin "1") (pinfunction "1_1") (pintype "passive"))
      (node (ref "JP15") (pin "1") (pinfunction "1_1") (pintype "passive"))
      (node (ref "JP16") (pin "1") (pinfunction "1_1") (pintype "passive"))
      (node (ref "JP20") (pin "1") (pinfunction "1_1") (pintype "passive"))
      (node (ref "JP22") (pin "1") (pinfunction "1_1") (pintype "passive"))
      (node (ref "JP23") (pin "1") (pinfunction "1_1") (pintype "passive"))
      (node (ref "JP27") (pin "1") (pinfunction "1_1") (pintype "passive"))
      (node (ref "JP28") (pin "1") (pinfunction "1_1") (pintype "passive"))
      (node (ref "JP3") (pin "1") (pinfunction "1_1") (pintype "passive"))
      (node (ref "JP32") (pin "1") (pinfunction "1_1") (pintype "passive"))
      (node (ref "JP34") (pin "1") (pinfunction "1_1") (pintype "passive"))
      (node (ref "JP35") (pin "1") (pinfunction "1_1") (pintype "passive"))
      (node (ref "JP6") (pin "1") (pinfunction "1_1") (pintype "passive"))
      (node (ref "JP9") (pin "1") (pinfunction "1_1") (pintype "passive"))
      (node (ref "Q10") (pin "2") (pinfunction "S_2") (pintype "bidirectional"))
      (node (ref "Q12") (pin "2") (pinfunction "S_2") (pintype "bidirectional"))
      (node (ref "Q14") (pin "2") (pinfunction "S_2") (pintype "bidirectional"))
      (node (ref "Q15") (pin "2") (pinfunction "S_2") (pintype "bidirectional"))
      (node (ref "Q17") (pin "2") (pinfunction "S_2") (pintype "bidirectional"))
      (node (ref "Q18") (pin "2") (pinfunction "S_2") (pintype "bidirectional"))
      (node (ref "Q19") (pin "2") (pinfunction "S_2") (pintype "bidirectional"))
      (node (ref "Q2") (pin "2") (pinfunction "S_2") (pintype "bidirectional"))
      (node (ref "Q20") (pin "2") (pinfunction "S_2") (pintype "bidirectional"))
      (node (ref "Q22") (pin "2") (pinfunction "S_2") (pintype "bidirectional"))
      (node (ref "Q23") (pin "2") (pinfunction "S_2") (pintype "bidirectional"))
      (node (ref "Q24") (pin "2") (pinfunction "S_2") (pintype "bidirectional"))
      (node (ref "Q4") (pin "2") (pinfunction "S_2") (pintype "bidirectional"))
      (node (ref "Q6") (pin "2") (pinfunction "S_2") (pintype "bidirectional"))
      (node (ref "Q8") (pin "2") (pinfunction "S_2") (pintype "bidirectional"))
      (node (ref "R1") (pin "2") (pinfunction "2_2") (pintype "passive"))
      (node (ref "R12") (pin "1") (pinfunction "1_1") (pintype "passive"))
      (node (ref "R13") (pin "2") (pinfunction "2_2") (pintype "passive"))
      (node (ref "R17") (pin "1") (pinfunction "1_1") (pintype "passive"))
      (node (ref "R2") (pin "1") (pinfunction "1_1") (pintype "passive"))
      (node (ref "R20") (pin "2") (pinfunction "2_2") (pintype "passive"))
      (node (ref "R22") (pin "1") (pinfunction "1_1") (pintype "passive"))
      (node (ref "R23") (pin "1") (pinfunction "1_1") (pintype "passive"))
      (node (ref "R31") (pin "1") (pinfunction "1_1") (pintype "passive"))
      (node (ref "R32") (pin "2") (pinfunction "2_2") (pintype "passive"))
      (node (ref "R35") (pin "1") (pinfunction "1_1") (pintype "passive"))
      (node (ref "R36") (pin "1") (pinfunction "1_1") (pintype "passive"))
      (node (ref "R4") (pin "1") (pinfunction "1_1") (pintype "passive"))
      (node (ref "R40") (pin "1") (pinfunction "1_1") (pintype "passive"))
      (node (ref "R41") (pin "1") (pinfunction "1_1") (pintype "passive"))
      (node (ref "R44") (pin "1") (pinfunction "1_1") (pintype "passive"))
      (node (ref "R45") (pin "1") (pinfunction "1_1") (pintype "passive"))
      (node (ref "R48") (pin "1") (pinfunction "1_1") (pintype "passive"))
      (node (ref "R50") (pin "1") (pinfunction "1_1") (pintype "passive"))
      (node (ref "R52") (pin "1") (pinfunction "1_1") (pintype "passive"))
      (node (ref "R53") (pin "1") (pinfunction "1_1") (pintype "passive"))
      (node (ref "R56") (pin "1") (pinfunction "1_1") (pintype "passive"))
      (node (ref "U1") (pin "4") (pinfunction "GND_4") (pintype "power_in"))
      (node (ref "U2") (pin "3") (pinfunction "A_3") (pintype "passive"))
      (node (ref "U3") (pin "2") (pinfunction "GND_2") (pintype "bidirectional"))
      (node (ref "U3") (pin "2@1") (pinfunction "GND_2@1") (pintype "bidirectional"))
      (node (ref "U4") (pin "2") (pinfunction "GND_2") (pintype "bidirectional"))
      (node (ref "U5") (pin "GND") (pinfunction "GND_GND") (pintype "bidirectional"))
      (node (ref "U5") (pin "GND2") (pinfunction "GND2_GND2") (pintype "bidirectional"))
      (node (ref "U5") (pin "GND4") (pinfunction "GND4_GND4") (pintype "bidirectional"))
    )
    (net (code "15") (name "Net-(D1-ANODE)") (class "Default")
      (node (ref "D1") (pin "A") (pinfunction "ANODE_A") (pintype "passive"))
      (node (ref "JP2") (pin "2") (pinfunction "2_2") (pintype "passive"))
      (node (ref "JP3") (pin "2") (pinfunction "2_2") (pintype "passive"))
    )
    (net (code "16") (name "Net-(D1-CATHODE)") (class "Default")
      (node (ref "D1") (pin "K") (pinfunction "CATHODE_K") (pintype "passive"))
      (node (ref "JP1") (pin "2") (pinfunction "2_2") (pintype "passive"))
      (node (ref "JP2") (pin "1") (pinfunction "1_1") (pintype "passive"))
    )
    (net (code "17") (name "Net-(D5-ANODE)") (class "Default")
      (node (ref "D5") (pin "A") (pinfunction "ANODE_A") (pintype "passive"))
      (node (ref "JP5") (pin "2") (pinfunction "2_2") (pintype "passive"))
      (node (ref "JP6") (pin "2") (pinfunction "2_2") (pintype "passive"))
    )
    (net (code "18") (name "Net-(D5-CATHODE)") (class "Default")
      (node (ref "D5") (pin "K") (pinfunction "CATHODE_K") (pintype "passive"))
      (node (ref "JP4") (pin "2") (pinfunction "2_2") (pintype "passive"))
      (node (ref "JP5") (pin "1") (pinfunction "1_1") (pintype "passive"))
    )
    (net (code "19") (name "Net-(D6-ANODE)") (class "Default")
      (node (ref "D6") (pin "A") (pinfunction "ANODE_A") (pintype "passive"))
      (node (ref "JP8") (pin "2") (pinfunction "2_2") (pintype "passive"))
      (node (ref "JP9") (pin "2") (pinfunction "2_2") (pintype "passive"))
    )
    (net (code "20") (name "Net-(D6-CATHODE)") (class "Default")
      (node (ref "D6") (pin "K") (pinfunction "CATHODE_K") (pintype "passive"))
      (node (ref "JP7") (pin "2") (pinfunction "2_2") (pintype "passive"))
      (node (ref "JP8") (pin "1") (pinfunction "1_1") (pintype "passive"))
    )
    (net (code "21") (name "Net-(D7-CATHODE)") (class "Default")
      (node (ref "C7") (pin "1") (pinfunction "1_1") (pintype "passive"))
      (node (ref "C8") (pin "1") (pinfunction "1_1") (pintype "passive"))
      (node (ref "C9") (pin "1") (pinfunction "1_1") (pintype "passive"))
      (node (ref "D7") (pin "K") (pinfunction "CATHODE_K") (pintype "passive"))
      (node (ref "D8") (pin "K") (pinfunction "CATHODE_K") (pintype "passive"))
      (node (ref "D9") (pin "K") (pinfunction "CATHODE_K") (pintype "passive"))
      (node (ref "L1") (pin "1") (pinfunction "P$1_1") (pintype "passive"))
      (node (ref "U4") (pin "4") (pinfunction "EN_4") (pintype "bidirectional"))
      (node (ref "U4") (pin "5") (pinfunction "VCC_5") (pintype "bidirectional"))
    )
    (net (code "22") (name "Net-(D10-ANODE)") (class "Default")
      (node (ref "D10") (pin "A") (pinfunction "ANODE_A") (pintype "passive"))
      (node (ref "JP11") (pin "2") (pinfunction "2_2") (pintype "passive"))
      (node (ref "JP12") (pin "2") (pinfunction "2_2") (pintype "passive"))
    )
    (net (code "23") (name "Net-(D10-CATHODE)") (class "Default")
      (node (ref "D10") (pin "K") (pinfunction "CATHODE_K") (pintype "passive"))
      (node (ref "JP10") (pin "2") (pinfunction "2_2") (pintype "passive"))
      (node (ref "JP11") (pin "1") (pinfunction "1_1") (pintype "passive"))
    )
    (net (code "24") (name "Net-(D11-ANODE)") (class "Default")
      (node (ref "D11") (pin "A") (pinfunction "ANODE_A") (pintype "passive"))
      (node (ref "L1") (pin "2") (pinfunction "P$2_2") (pintype "passive"))
      (node (ref "U4") (pin "1") (pinfunction "LX_1") (pintype "bidirectional"))
    )
    (net (code "25") (name "Net-(D12-ANODE)") (class "Default")
      (node (ref "D12") (pin "A") (pinfunction "ANODE_A") (pintype "passive"))
      (node (ref "JP14") (pin "2") (pinfunction "2_2") (pintype "passive"))
      (node (ref "JP15") (pin "2") (pinfunction "2_2") (pintype "passive"))
    )
    (net (code "26") (name "Net-(D12-CATHODE)") (class "Default")
      (node (ref "D12") (pin "K") (pinfunction "CATHODE_K") (pintype "passive"))
      (node (ref "JP13") (pin "2") (pinfunction "2_2") (pintype "passive"))
      (node (ref "JP14") (pin "1") (pinfunction "1_1") (pintype "passive"))
    )
    (net (code "27") (name "Net-(D13-ANODE)") (class "Default")
      (node (ref "D13") (pin "A") (pinfunction "ANODE_A") (pintype "passive"))
      (node (ref "JP19") (pin "2") (pinfunction "2_2") (pintype "passive"))
      (node (ref "JP22") (pin "2") (pinfunction "2_2") (pintype "passive"))
    )
    (net (code "28") (name "Net-(D13-CATHODE)") (class "Default")
      (node (ref "D13") (pin "K") (pinfunction "CATHODE_K") (pintype "passive"))
      (node (ref "JP17") (pin "2") (pinfunction "2_2") (pintype "passive"))
      (node (ref "JP19") (pin "1") (pinfunction "1_1") (pintype "passive"))
    )
    (net (code "29") (name "Net-(D14-ANODE)") (class "Default")
      (node (ref "D14") (pin "A") (pinfunction "ANODE_A") (pintype "passive"))
      (node (ref "JP31") (pin "2") (pinfunction "2_2") (pintype "passive"))
      (node (ref "JP34") (pin "2") (pinfunction "2_2") (pintype "passive"))
    )
    (net (code "30") (name "Net-(D14-CATHODE)") (class "Default")
      (node (ref "D14") (pin "K") (pinfunction "CATHODE_K") (pintype "passive"))
      (node (ref "JP29") (pin "2") (pinfunction "2_2") (pintype "passive"))
      (node (ref "JP31") (pin "1") (pinfunction "1_1") (pintype "passive"))
    )
    (net (code "31") (name "Net-(JP18-Pad2)") (class "Default")
      (node (ref "JP18") (pin "2") (pinfunction "2_2") (pintype "passive"))
      (node (ref "R43") (pin "2") (pinfunction "2_2") (pintype "passive"))
    )
    (net (code "32") (name "Net-(JP21-Pad2)") (class "Default")
      (node (ref "JP21") (pin "2") (pinfunction "2_2") (pintype "passive"))
      (node (ref "R46") (pin "2") (pinfunction "2_2") (pintype "passive"))
    )
    (net (code "33") (name "Net-(JP24-Pad2)") (class "Default")
      (node (ref "JP24") (pin "2") (pinfunction "2_2") (pintype "passive"))
      (node (ref "R49") (pin "2") (pinfunction "2_2") (pintype "passive"))
    )
    (net (code "34") (name "Net-(JP30-Pad2)") (class "Default")
      (node (ref "JP30") (pin "2") (pinfunction "2_2") (pintype "passive"))
      (node (ref "R51") (pin "2") (pinfunction "2_2") (pintype "passive"))
    )
    (net (code "35") (name "Net-(JP33-Pad2)") (class "Default")
      (node (ref "JP33") (pin "2") (pinfunction "2_2") (pintype "passive"))
      (node (ref "R54") (pin "2") (pinfunction "2_2") (pintype "passive"))
    )
    (net (code "36") (name "Net-(JP36-Pad2)") (class "Default")
      (node (ref "JP36") (pin "2") (pinfunction "2_2") (pintype "passive"))
      (node (ref "R57") (pin "2") (pinfunction "2_2") (pintype "passive"))
    )
    (net (code "37") (name "Net-(Q1-D)") (class "Default")
      (node (ref "JP1") (pin "1") (pinfunction "1_1") (pintype "passive"))
      (node (ref "Q1") (pin "3") (pinfunction "D_3") (pintype "bidirectional"))
    )
    (net (code "38") (name "Net-(Q1-G)") (class "Default")
      (node (ref "JP3") (pin "3") (pinfunction "3_3") (pintype "passive"))
      (node (ref "Q1") (pin "1") (pinfunction "G_1") (pintype "bidirectional"))
      (node (ref "Q2") (pin "3") (pinfunction "D_3") (pintype "bidirectional"))
      (node (ref "R5") (pin "2") (pinfunction "2_2") (pintype "passive"))
    )
    (net (code "39") (name "Net-(Q3-G)") (class "Default")
      (node (ref "Q3") (pin "4") (pinfunction "G_4") (pintype "bidirectional"))
      (node (ref "Q4") (pin "3") (pinfunction "D_3") (pintype "bidirectional"))
      (node (ref "R6") (pin "1") (pinfunction "1_1") (pintype "passive"))
    )
    (net (code "40") (name "Net-(Q3-S-Pad1)") (class "Default")
      (node (ref "Q3") (pin "1") (pinfunction "S_1") (pintype "bidirectional"))
      (node (ref "Q3") (pin "2") (pinfunction "S_2") (pintype "bidirectional"))
      (node (ref "Q3") (pin "3") (pinfunction "S_3") (pintype "bidirectional"))
      (node (ref "R10") (pin "2") (pinfunction "2_2") (pintype "passive"))
      (node (ref "R6") (pin "2") (pinfunction "2_2") (pintype "passive"))
      (node (ref "R7") (pin "1") (pinfunction "1_1") (pintype "passive"))
      (node (ref "R8") (pin "1") (pinfunction "1_1") (pintype "passive"))
    )
    (net (code "41") (name "Net-(Q5-D)") (class "Default")
      (node (ref "JP4") (pin "1") (pinfunction "1_1") (pintype "passive"))
      (node (ref "Q5") (pin "3") (pinfunction "D_3") (pintype "bidirectional"))
    )
    (net (code "42") (name "Net-(Q5-G)") (class "Default")
      (node (ref "JP6") (pin "3") (pinfunction "3_3") (pintype "passive"))
      (node (ref "Q5") (pin "1") (pinfunction "G_1") (pintype "bidirectional"))
      (node (ref "Q6") (pin "3") (pinfunction "D_3") (pintype "bidirectional"))
      (node (ref "R15") (pin "2") (pinfunction "2_2") (pintype "passive"))
    )
    (net (code "43") (name "Net-(Q7-D)") (class "Default")
      (node (ref "JP7") (pin "1") (pinfunction "1_1") (pintype "passive"))
      (node (ref "Q7") (pin "3") (pinfunction "D_3") (pintype "bidirectional"))
    )
    (net (code "44") (name "Net-(Q7-G)") (class "Default")
      (node (ref "JP9") (pin "3") (pinfunction "3_3") (pintype "passive"))
      (node (ref "Q7") (pin "1") (pinfunction "G_1") (pintype "bidirectional"))
      (node (ref "Q8") (pin "3") (pinfunction "D_3") (pintype "bidirectional"))
      (node (ref "R19") (pin "2") (pinfunction "2_2") (pintype "passive"))
    )
    (net (code "45") (name "Net-(Q9-S-Pad1)") (class "Default")
      (node (ref "Q9") (pin "1") (pinfunction "S_1") (pintype "bidirectional"))
      (node (ref "Q9") (pin "2") (pinfunction "S_2") (pintype "bidirectional"))
      (node (ref "Q9") (pin "3") (pinfunction "S_3") (pintype "bidirectional"))
      (node (ref "R24") (pin "2") (pinfunction "2_2") (pintype "passive"))
      (node (ref "R26") (pin "1") (pinfunction "1_1") (pintype "passive"))
      (node (ref "R27") (pin "1") (pinfunction "1_1") (pintype "passive"))
      (node (ref "R28") (pin "2") (pinfunction "2_2") (pintype "passive"))
    )
    (net (code "46") (name "Net-(Q10-D)") (class "Default")
      (node (ref "Q10") (pin "3") (pinfunction "D_3") (pintype "bidirectional"))
      (node (ref "Q9") (pin "4") (pinfunction "G_4") (pintype "bidirectional"))
      (node (ref "R24") (pin "1") (pinfunction "1_1") (pintype "passive"))
    )
    (net (code "47") (name "Net-(Q11-D)") (class "Default")
      (node (ref "JP10") (pin "1") (pinfunction "1_1") (pintype "passive"))
      (node (ref "Q11") (pin "3") (pinfunction "D_3") (pintype "bidirectional"))
    )
    (net (code "48") (name "Net-(Q11-G)") (class "Default")
      (node (ref "JP12") (pin "3") (pinfunction "3_3") (pintype "passive"))
      (node (ref "Q11") (pin "1") (pinfunction "G_1") (pintype "bidirectional"))
      (node (ref "Q12") (pin "3") (pinfunction "D_3") (pintype "bidirectional"))
      (node (ref "R25") (pin "2") (pinfunction "2_2") (pintype "passive"))
    )
    (net (code "49") (name "Net-(Q13-D)") (class "Default")
      (node (ref "JP13") (pin "1") (pinfunction "1_1") (pintype "passive"))
      (node (ref "Q13") (pin "3") (pinfunction "D_3") (pintype "bidirectional"))
    )
    (net (code "50") (name "Net-(Q13-G)") (class "Default")
      (node (ref "JP15") (pin "3") (pinfunction "3_3") (pintype "passive"))
      (node (ref "Q13") (pin "1") (pinfunction "G_1") (pintype "bidirectional"))
      (node (ref "Q14") (pin "3") (pinfunction "D_3") (pintype "bidirectional"))
      (node (ref "R38") (pin "2") (pinfunction "2_2") (pintype "passive"))
    )
    (net (code "51") (name "Net-(Q15-D)") (class "Default")
      (node (ref "JP16") (pin "2") (pinfunction "2_2") (pintype "passive"))
      (node (ref "Q15") (pin "3") (pinfunction "D_3") (pintype "bidirectional"))
      (node (ref "R43") (pin "1") (pinfunction "1_1") (pintype "passive"))
    )
    (net (code "52") (name "Net-(Q16-D)") (class "Default")
      (node (ref "JP17") (pin "1") (pinfunction "1_1") (pintype "passive"))
      (node (ref "Q16") (pin "3") (pinfunction "D_3") (pintype "bidirectional"))
    )
    (net (code "53") (name "Net-(Q16-G)") (class "Default")
      (node (ref "JP22") (pin "3") (pinfunction "3_3") (pintype "passive"))
      (node (ref "Q16") (pin "1") (pinfunction "G_1") (pintype "bidirectional"))
      (node (ref "Q18") (pin "3") (pinfunction "D_3") (pintype "bidirectional"))
      (node (ref "R47") (pin "2") (pinfunction "2_2") (pintype "passive"))
    )
    (net (code "54") (name "Net-(Q17-D)") (class "Default")
      (node (ref "JP20") (pin "2") (pinfunction "2_2") (pintype "passive"))
      (node (ref "Q17") (pin "3") (pinfunction "D_3") (pintype "bidirectional"))
      (node (ref "R46") (pin "1") (pinfunction "1_1") (pintype "passive"))
    )
    (net (code "55") (name "Net-(Q19-D)") (class "Default")
      (node (ref "JP23") (pin "2") (pinfunction "2_2") (pintype "passive"))
      (node (ref "Q19") (pin "3") (pinfunction "D_3") (pintype "bidirectional"))
      (node (ref "R49") (pin "1") (pinfunction "1_1") (pintype "passive"))
    )
    (net (code "56") (name "Net-(Q20-D)") (class "Default")
      (node (ref "JP27") (pin "2") (pinfunction "2_2") (pintype "passive"))
      (node (ref "Q20") (pin "3") (pinfunction "D_3") (pintype "bidirectional"))
      (node (ref "R51") (pin "1") (pinfunction "1_1") (pintype "passive"))
    )
    (net (code "57") (name "Net-(Q21-D)") (class "Default")
      (node (ref "JP29") (pin "1") (pinfunction "1_1") (pintype "passive"))
      (node (ref "Q21") (pin "3") (pinfunction "D_3") (pintype "bidirectional"))
    )
    (net (code "58") (name "Net-(Q21-G)") (class "Default")
      (node (ref "JP34") (pin "3") (pinfunction "3_3") (pintype "passive"))
      (node (ref "Q21") (pin "1") (pinfunction "G_1") (pintype "bidirectional"))
      (node (ref "Q23") (pin "3") (pinfunction "D_3") (pintype "bidirectional"))
      (node (ref "R55") (pin "2") (pinfunction "2_2") (pintype "passive"))
    )
    (net (code "59") (name "Net-(Q22-D)") (class "Default")
      (node (ref "JP32") (pin "2") (pinfunction "2_2") (pintype "passive"))
      (node (ref "Q22") (pin "3") (pinfunction "D_3") (pintype "bidirectional"))
      (node (ref "R54") (pin "1") (pinfunction "1_1") (pintype "passive"))
    )
    (net (code "60") (name "Net-(Q24-D)") (class "Default")
      (node (ref "JP35") (pin "2") (pinfunction "2_2") (pintype "passive"))
      (node (ref "Q24") (pin "3") (pinfunction "D_3") (pintype "bidirectional"))
      (node (ref "R57") (pin "1") (pinfunction "1_1") (pintype "passive"))
    )
    (net (code "61") (name "Net-(U1A-VIN+)") (class "Default")
      (node (ref "R11") (pin "1") (pinfunction "1_1") (pintype "passive"))
      (node (ref "R13") (pin "1") (pinfunction "1_1") (pintype "passive"))
      (node (ref "U1") (pin "3") (pinfunction "VIN+_3") (pintype "bidirectional"))
    )
    (net (code "62") (name "Net-(U1A-VIN-)") (class "Default")
      (node (ref "R10") (pin "1") (pinfunction "1_1") (pintype "passive"))
      (node (ref "R14") (pin "1") (pinfunction "1_1") (pintype "passive"))
      (node (ref "U1") (pin "2") (pinfunction "VIN-_2") (pintype "bidirectional"))
    )
    (net (code "63") (name "Net-(U1A-VOUT)") (class "Default")
      (node (ref "R14") (pin "2") (pinfunction "2_2") (pintype "passive"))
      (node (ref "R16") (pin "1") (pinfunction "1_1") (pintype "passive"))
      (node (ref "U1") (pin "1") (pinfunction "VOUT_1") (pintype "bidirectional"))
    )
    (net (code "64") (name "Net-(U1B-VIN+)") (class "Default")
      (node (ref "R29") (pin "1") (pinfunction "1_1") (pintype "passive"))
      (node (ref "R32") (pin "1") (pinfunction "1_1") (pintype "passive"))
      (node (ref "U1") (pin "5") (pinfunction "VIN+_5") (pintype "bidirectional"))
    )
    (net (code "65") (name "Net-(U1B-VIN-)") (class "Default")
      (node (ref "R28") (pin "1") (pinfunction "1_1") (pintype "passive"))
      (node (ref "R34") (pin "1") (pinfunction "1_1") (pintype "passive"))
      (node (ref "U1") (pin "6") (pinfunction "VIN-_6") (pintype "bidirectional"))
    )
    (net (code "66") (name "Net-(U1B-VOUT)") (class "Default")
      (node (ref "R34") (pin "2") (pinfunction "2_2") (pintype "passive"))
      (node (ref "R37") (pin "1") (pinfunction "1_1") (pintype "passive"))
      (node (ref "U1") (pin "7") (pinfunction "VOUT_7") (pintype "bidirectional"))
    )
    (net (code "67") (name "Net-(U4-FB)") (class "Default")
      (node (ref "R39") (pin "1") (pinfunction "1_1") (pintype "passive"))
      (node (ref "R40") (pin "2") (pinfunction "2_2") (pintype "passive"))
      (node (ref "U4") (pin "3") (pinfunction "FB_3") (pintype "bidirectional"))
    )
    (net (code "68") (name "Net-(U4-OC)") (class "Default")
      (node (ref "R35") (pin "2") (pinfunction "2_2") (pintype "passive"))
      (node (ref "U4") (pin "6") (pinfunction "OC_6") (pintype "bidirectional"))
    )
    (net (code "69") (name "Net-(U5-A12{slash}D+)") (class "Default")
      (node (ref "R42") (pin "2") (pinfunction "2_2") (pintype "passive"))
      (node (ref "U5") (pin "A12") (pinfunction "A12/D+_A12") (pintype "bidirectional"))
    )
    (net (code "70") (name "OD_1") (class "Default")
      (node (ref "Q24") (pin "1") (pinfunction "G_1") (pintype "bidirectional"))
      (node (ref "R56") (pin "2") (pinfunction "2_2") (pintype "passive"))
      (node (ref "U5") (pin "B12") (pinfunction "B12_B12") (pintype "bidirectional"))
    )
    (net (code "71") (name "OD_2") (class "Default")
      (node (ref "Q22") (pin "1") (pinfunction "G_1") (pintype "bidirectional"))
      (node (ref "R52") (pin "2") (pinfunction "2_2") (pintype "passive"))
      (node (ref "U5") (pin "B14") (pinfunction "B14_B14") (pintype "bidirectional"))
    )
    (net (code "72") (name "OD_3") (class "Default")
      (node (ref "Q20") (pin "1") (pinfunction "G_1") (pintype "bidirectional"))
      (node (ref "R50") (pin "2") (pinfunction "2_2") (pintype "passive"))
      (node (ref "U5") (pin "A8") (pinfunction "A8_A8") (pintype "bidirectional"))
    )
    (net (code "73") (name "OD_4") (class "Default")
      (node (ref "Q19") (pin "1") (pinfunction "G_1") (pintype "bidirectional"))
      (node (ref "R48") (pin "2") (pinfunction "2_2") (pintype "passive"))
      (node (ref "U5") (pin "A10") (pinfunction "A10_A10") (pintype "bidirectional"))
    )
    (net (code "74") (name "OD_5") (class "Default")
      (node (ref "Q17") (pin "1") (pinfunction "G_1") (pintype "bidirectional"))
      (node (ref "R44") (pin "2") (pinfunction "2_2") (pintype "passive"))
      (node (ref "U5") (pin "B3") (pinfunction "B3_B3") (pintype "bidirectional"))
    )
    (net (code "75") (name "OD_6") (class "Default")
      (node (ref "Q15") (pin "1") (pinfunction "G_1") (pintype "bidirectional"))
      (node (ref "R41") (pin "2") (pinfunction "2_2") (pintype "passive"))
      (node (ref "U5") (pin "B5") (pinfunction "B5_B5") (pintype "bidirectional"))
    )
    (net (code "76") (name "RLY_1") (class "Default")
      (node (ref "Q2") (pin "1") (pinfunction "G_1") (pintype "bidirectional"))
      (node (ref "R2") (pin "2") (pinfunction "2_2") (pintype "passive"))
      (node (ref "U5") (pin "B13") (pinfunction "B13_B13") (pintype "bidirectional"))
    )
    (net (code "77") (name "RLY_2") (class "Default")
      (node (ref "Q6") (pin "1") (pinfunction "G_1") (pintype "bidirectional"))
      (node (ref "R12") (pin "2") (pinfunction "2_2") (pintype "passive"))
      (node (ref "U5") (pin "B15") (pinfunction "B15_B15") (pintype "bidirectional"))
    )
    (net (code "78") (name "RLY_3") (class "Default")
      (node (ref "Q8") (pin "1") (pinfunction "G_1") (pintype "bidirectional"))
      (node (ref "R17") (pin "2") (pinfunction "2_2") (pintype "passive"))
      (node (ref "U5") (pin "A9") (pinfunction "A9_A9") (pintype "bidirectional"))
    )
    (net (code "79") (name "RLY_4") (class "Default")
      (node (ref "Q12") (pin "1") (pinfunction "G_1") (pintype "bidirectional"))
      (node (ref "R23") (pin "2") (pinfunction "2_2") (pintype "passive"))
      (node (ref "U5") (pin "A15") (pinfunction "A15_A15") (pintype "bidirectional"))
    )
    (net (code "80") (name "RLY_5") (class "Default")
      (node (ref "Q14") (pin "1") (pinfunction "G_1") (pintype "bidirectional"))
      (node (ref "R36") (pin "2") (pinfunction "2_2") (pintype "passive"))
      (node (ref "U5") (pin "B4") (pinfunction "B4_B4") (pintype "bidirectional"))
    )
    (net (code "81") (name "RLY_6") (class "Default")
      (node (ref "Q18") (pin "1") (pinfunction "G_1") (pintype "bidirectional"))
      (node (ref "R45") (pin "2") (pinfunction "2_2") (pintype "passive"))
      (node (ref "U5") (pin "B6") (pinfunction "B6_B6") (pintype "bidirectional"))
    )
    (net (code "82") (name "RLY_7") (class "Default")
      (node (ref "Q23") (pin "1") (pinfunction "G_1") (pintype "bidirectional"))
      (node (ref "R53") (pin "2") (pinfunction "2_2") (pintype "passive"))
      (node (ref "U5") (pin "B7") (pinfunction "B7_B7") (pintype "bidirectional"))
    )
    (net (code "83") (name "SSRX+") (class "Default")
      (node (ref "CON3") (pin "6-SSRX+") (pinfunction "SSRX+_6-SSRX+") (pintype "bidirectional"))
      (node (ref "CON4") (pin "6-SSRX+") (pinfunction "SSRX+_6-SSRX+") (pintype "bidirectional"))
    )
    (net (code "84") (name "SSRX-") (class "Default")
      (node (ref "CON3") (pin "5-SSRX-") (pinfunction "SSRX-_5-SSRX-") (pintype "bidirectional"))
      (node (ref "CON4") (pin "5-SSRX-") (pinfunction "SSRX-_5-SSRX-") (pintype "bidirectional"))
    )
    (net (code "85") (name "SSTX+") (class "Default")
      (node (ref "CON3") (pin "9-SSTX+") (pinfunction "SSTX+_9-SSTX+") (pintype "bidirectional"))
      (node (ref "CON4") (pin "9-SSTX+") (pinfunction "SSTX+_9-SSTX+") (pintype "bidirectional"))
    )
    (net (code "86") (name "SSTX-") (class "Default")
      (node (ref "CON3") (pin "8-SSTX-") (pinfunction "SSTX-_8-SSTX-") (pintype "bidirectional"))
      (node (ref "CON4") (pin "8-SSTX-") (pinfunction "SSTX-_8-SSTX-") (pintype "bidirectional"))
    )
    (net (code "87") (name "USB2-EN") (class "Default")
      (node (ref "Q4") (pin "1") (pinfunction "G_1") (pintype "bidirectional"))
      (node (ref "R1") (pin "1") (pinfunction "1_1") (pintype "passive"))
      (node (ref "U5") (pin "B11") (pinfunction "B11_B11") (pintype "bidirectional"))
    )
    (net (code "88") (name "USB2-ISNS") (class "Default")
      (node (ref "C4") (pin "1") (pinfunction "1_1") (pintype "passive"))
      (node (ref "R16") (pin "2") (pinfunction "2_2") (pintype "passive"))
      (node (ref "U5") (pin "B1") (pinfunction "B1_B1") (pintype "bidirectional"))
    )
    (net (code "89") (name "USB2-TSNS") (class "Default")
      (node (ref "C3") (pin "1") (pinfunction "1_1") (pintype "passive"))
      (node (ref "J1") (pin "2") (pinfunction "2_2") (pintype "passive"))
      (node (ref "R9") (pin "1") (pinfunction "1_1") (pintype "passive"))
      (node (ref "U5") (pin "A3") (pinfunction "A3_A3") (pintype "bidirectional"))
    )
    (net (code "90") (name "USB2-VCC-SW") (class "Default")
      (node (ref "CON1") (pin "1-5V") (pinfunction "VCC_1-5V") (pintype "bidirectional"))
      (node (ref "Q3") (pin "5") (pinfunction "D_5") (pintype "bidirectional"))
      (node (ref "Q3") (pin "6") (pinfunction "D_6") (pintype "bidirectional"))
      (node (ref "Q3") (pin "7") (pinfunction "D_7") (pintype "bidirectional"))
      (node (ref "Q3") (pin "8") (pinfunction "D_8") (pintype "bidirectional"))
      (node (ref "R3") (pin "2") (pinfunction "2_2") (pintype "passive"))
    )
    (net (code "91") (name "USB2-VSNS") (class "Default")
      (node (ref "C2") (pin "1") (pinfunction "1_1") (pintype "passive"))
      (node (ref "R3") (pin "1") (pinfunction "1_1") (pintype "passive"))
      (node (ref "R4") (pin "2") (pinfunction "2_2") (pintype "passive"))
      (node (ref "U5") (pin "B0") (pinfunction "B0_B0") (pintype "bidirectional"))
    )
    (net (code "92") (name "USB2VIN") (class "Default")
      (node (ref "CON2") (pin "1-VCC") (pinfunction "VCC_1-VCC") (pintype "bidirectional"))
      (node (ref "D2") (pin "A") (pinfunction "ANODE_A") (pintype "passive"))
      (node (ref "D9") (pin "A") (pinfunction "ANODE_A") (pintype "passive"))
      (node (ref "R11") (pin "2") (pinfunction "2_2") (pintype "passive"))
      (node (ref "R7") (pin "2") (pinfunction "2_2") (pintype "passive"))
      (node (ref "R8") (pin "2") (pinfunction "2_2") (pintype "passive"))
    )
    (net (code "93") (name "USB3-EN") (class "Default")
      (node (ref "Q10") (pin "1") (pinfunction "G_1") (pintype "bidirectional"))
      (node (ref "R20") (pin "1") (pinfunction "1_1") (pintype "passive"))
      (node (ref "U5") (pin "B10") (pinfunction "B10_B10") (pintype "bidirectional"))
    )
    (net (code "94") (name "USB3-ISNS") (class "Default")
      (node (ref "C14") (pin "1") (pinfunction "1_1") (pintype "passive"))
      (node (ref "R37") (pin "2") (pinfunction "2_2") (pintype "passive"))
      (node (ref "U5") (pin "A7") (pinfunction "A7_A7") (pintype "bidirectional"))
    )
    (net (code "95") (name "USB3-TSNS") (class "Default")
      (node (ref "C11") (pin "1") (pinfunction "1_1") (pintype "passive"))
      (node (ref "J2") (pin "2") (pinfunction "2_2") (pintype "passive"))
      (node (ref "R30") (pin "1") (pinfunction "1_1") (pintype "passive"))
      (node (ref "U5") (pin "A2") (pinfunction "A2_A2") (pintype "bidirectional"))
    )
    (net (code "96") (name "USB3-VCC-SW") (class "Default")
      (node (ref "CON3") (pin "1-VBUS") (pinfunction "VBUS_1-VBUS") (pintype "bidirectional"))
      (node (ref "Q9") (pin "5") (pinfunction "D_5") (pintype "bidirectional"))
      (node (ref "Q9") (pin "6") (pinfunction "D_6") (pintype "bidirectional"))
      (node (ref "Q9") (pin "7") (pinfunction "D_7") (pintype "bidirectional"))
      (node (ref "Q9") (pin "8") (pinfunction "D_8") (pintype "bidirectional"))
      (node (ref "R21") (pin "2") (pinfunction "2_2") (pintype "passive"))
    )
    (net (code "97") (name "USB3-VSNS") (class "Default")
      (node (ref "C6") (pin "1") (pinfunction "1_1") (pintype "passive"))
      (node (ref "R21") (pin "1") (pinfunction "1_1") (pintype "passive"))
      (node (ref "R22") (pin "2") (pinfunction "2_2") (pintype "passive"))
      (node (ref "U5") (pin "A6") (pinfunction "A6_A6") (pintype "bidirectional"))
    )
    (net (code "98") (name "USB3VIN") (class "Default")
      (node (ref "CON4") (pin "1-VBUS") (pinfunction "VBUS_1-VBUS") (pintype "bidirectional"))
      (node (ref "D3") (pin "A") (pinfunction "ANODE_A") (pintype "passive"))
      (node (ref "D8") (pin "A") (pinfunction "ANODE_A") (pintype "passive"))
      (node (ref "R26") (pin "2") (pinfunction "2_2") (pintype "passive"))
      (node (ref "R27") (pin "2") (pinfunction "2_2") (pintype "passive"))
      (node (ref "R29") (pin "2") (pinfunction "2_2") (pintype "passive"))
    )
    (net (code "99") (name "USBBPIN") (class "Default")
      (node (ref "C16") (pin "1") (pinfunction "1_1") (pintype "passive"))
      (node (ref "C5") (pin "1") (pinfunction "1_1") (pintype "passive"))
      (node (ref "D4") (pin "A") (pinfunction "ANODE_A") (pintype "passive"))
      (node (ref "D7") (pin "A") (pinfunction "ANODE_A") (pintype "passive"))
      (node (ref "JP18") (pin "1") (pinfunction "1_1") (pintype "passive"))
      (node (ref "JP21") (pin "1") (pinfunction "1_1") (pintype "passive"))
      (node (ref "JP24") (pin "1") (pinfunction "1_1") (pintype "passive"))
      (node (ref "JP28") (pin "3") (pinfunction "3_3") (pintype "passive"))
      (node (ref "JP30") (pin "1") (pinfunction "1_1") (pintype "passive"))
      (node (ref "JP33") (pin "1") (pinfunction "1_1") (pintype "passive"))
      (node (ref "JP36") (pin "1") (pinfunction "1_1") (pintype "passive"))
      (node (ref "R18") (pin "1") (pinfunction "1_1") (pintype "passive"))
      (node (ref "U3") (pin "3") (pinfunction "VIN_3") (pintype "bidirectional"))
      (node (ref "U5") (pin "5V") (pinfunction "5V_5V") (pintype "bidirectional"))
    )
    (net (code "100") (name "VUSBMAX") (class "Default")
      (node (ref "C1") (pin "1") (pinfunction "1_1") (pintype "passive"))
      (node (ref "D2") (pin "K") (pinfunction "CATHODE_K") (pintype "passive"))
      (node (ref "D3") (pin "K") (pinfunction "CATHODE_K") (pintype "passive"))
      (node (ref "D4") (pin "K") (pinfunction "CATHODE_K") (pintype "passive"))
      (node (ref "U1") (pin "8") (pinfunction "VCC_8") (pintype "power_in"))
    )
    (net (code "101") (name "unconnected-(CON2-ID-Pad4-ID)") (class "Default")
      (node (ref "CON2") (pin "4-ID") (pinfunction "ID_4-ID") (pintype "bidirectional"))
    )
    (net (code "102") (name "unconnected-(U5-PadRST)") (class "Default")
      (node (ref "U5") (pin "RST") (pinfunction "RST_RST") (pintype "bidirectional"))
    )
    (net (code "103") (name "unconnected-(U5-VB-PadVBAT)") (class "Default")
      (node (ref "U5") (pin "VBAT") (pinfunction "VB_VBAT") (pintype "bidirectional"))
    )
  )
)
